# No_Opto_Flyback.net
KiCad netlist of a schematic drawn in Altium Designer
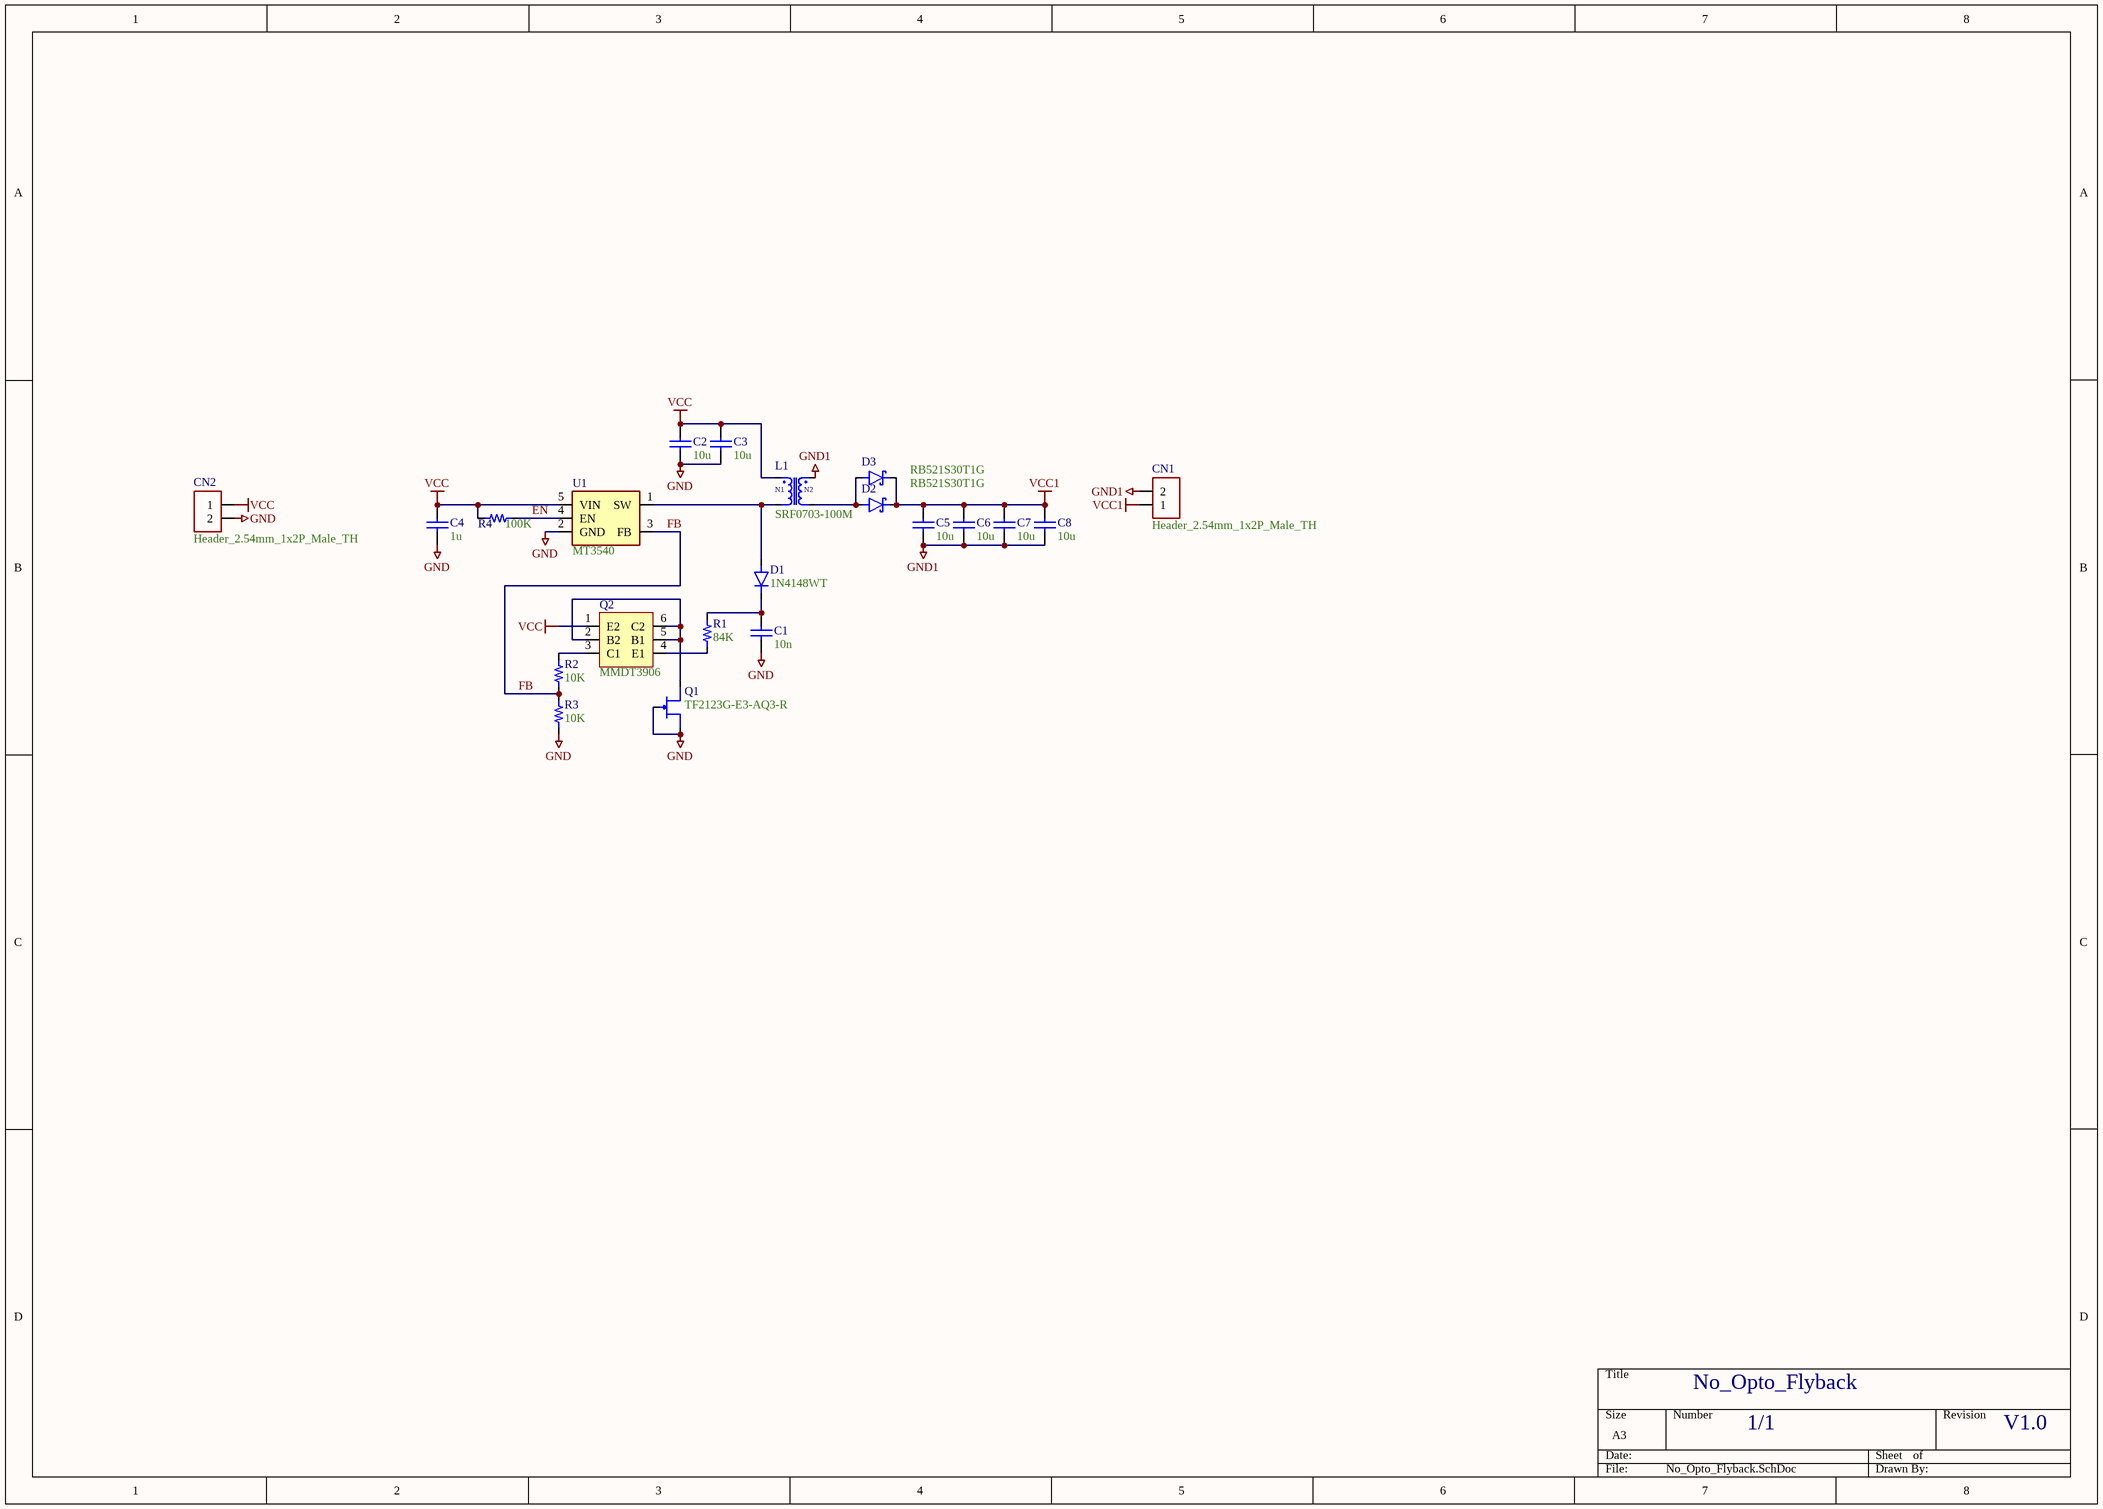
[diagram p0: No_Opto_Flyback.SchDoc]

(export (version "E")
  (design (tool "Eeschema 10.0.6"))
  (components
    (comp (ref "C1")
      (value "10n")
      (footprint "CAP_0402")
      (description "Capacitor")
      (fields (field (name "VOLTAGE") "V"))
      (libsource (lib "Passive") (part "Capacitor"))
    )
    (comp (ref "C2")
      (value "10u")
      (footprint "CAP_0603")
      (description "Capacitor")
      (fields (field (name "VOLTAGE") "V"))
      (libsource (lib "Passive") (part "Capacitor"))
    )
    (comp (ref "C3")
      (value "10u")
      (footprint "CAP_0603")
      (description "Capacitor")
      (fields (field (name "VOLTAGE") "V"))
      (libsource (lib "Passive") (part "Capacitor"))
    )
    (comp (ref "C4")
      (value "1u")
      (footprint "CAP_0402")
      (description "Capacitor")
      (fields (field (name "VOLTAGE") "V"))
      (libsource (lib "Passive") (part "Capacitor"))
    )
    (comp (ref "C5")
      (value "10u")
      (footprint "CAP_0603")
      (description "Capacitor")
      (fields (field (name "VOLTAGE") "V"))
      (libsource (lib "Passive") (part "Capacitor"))
    )
    (comp (ref "C6")
      (value "10u")
      (footprint "CAP_0603")
      (description "Capacitor")
      (fields (field (name "VOLTAGE") "V"))
      (libsource (lib "Passive") (part "Capacitor"))
    )
    (comp (ref "C7")
      (value "10u")
      (footprint "CAP_0603")
      (description "Capacitor")
      (fields (field (name "VOLTAGE") "V"))
      (libsource (lib "Passive") (part "Capacitor"))
    )
    (comp (ref "C8")
      (value "10u")
      (footprint "CAP_0603")
      (description "Capacitor")
      (fields (field (name "VOLTAGE") "V"))
      (libsource (lib "Passive") (part "Capacitor"))
    )
    (comp (ref "CN1")
      (value "Header_2.54mm_1x2P_Male_TH")
      (footprint "Header_2.54mm_1x2P_Male_TH")
      (description "Header_2.54mm_1x2P_Male\r\nThrough-hole")
      (libsource (lib "Connector") (part "Header_2.54mm_1x2P_Male_TH"))
    )
    (comp (ref "CN2")
      (value "Header_2.54mm_1x2P_Male_TH")
      (footprint "Header_2.54mm_1x2P_Male_TH")
      (description "Header_2.54mm_1x2P_Male\r\nThrough-hole")
      (libsource (lib "Connector") (part "Header_2.54mm_1x2P_Male_TH"))
    )
    (comp (ref "D1")
      (value "1N4148WT")
      (footprint "SOD-523-2")
      (description "Signal Diode")
      (libsource (lib "Diode") (part "1N4148WT"))
    )
    (comp (ref "D2")
      (value "RB521S30T1G")
      (footprint "SOD-523-2")
      (description "Schottky Diode")
      (libsource (lib "Diode") (part "RB521S30T1G"))
    )
    (comp (ref "D3")
      (value "RB521S30T1G")
      (footprint "SOD-523-2")
      (description "Schottky Diode")
      (libsource (lib "Diode") (part "RB521S30T1G"))
    )
    (comp (ref "L1")
      (value "SRF0703-100M")
      (footprint "SRF0703")
      (libsource (lib "Passive") (part "SRF0703-100M"))
    )
    (comp (ref "Q1")
      (value "TF2123G-E3-AQ3-R")
      (footprint "SOT-723-3_120X80X50_40P")
      (description "N-JFET")
      (libsource (lib "Transistor") (part "TF2123G-E3-AQ3-R"))
    )
    (comp (ref "Q2")
      (value "MMDT3906")
      (footprint "SOT-363-6_215X130X110_65P")
      (description "Double PNP")
      (libsource (lib "Transistor") (part "MMDT3906"))
    )
    (comp (ref "R1")
      (value "84K")
      (footprint "RES_0402")
      (description "Resistor")
      (fields (field (name "VOLTAGE") "V"))
      (libsource (lib "Passive") (part "Resistor"))
    )
    (comp (ref "R2")
      (value "10K")
      (footprint "RES_0402")
      (description "Resistor")
      (fields (field (name "VOLTAGE") "V"))
      (libsource (lib "Passive") (part "Resistor"))
    )
    (comp (ref "R3")
      (value "10K")
      (footprint "RES_0402")
      (description "Resistor")
      (fields (field (name "VOLTAGE") "V"))
      (libsource (lib "Passive") (part "Resistor"))
    )
    (comp (ref "R4")
      (value "100K")
      (footprint "RES_0402")
      (description "Resistor")
      (fields (field (name "VOLTAGE") "V"))
      (libsource (lib "Passive") (part "Resistor"))
    )
    (comp (ref "U1")
      (value "MT3540")
      (footprint "SOT-23-5_290X160X120_95P")
      (description "Asynchronous Boost Convertor\r\nVin:2.5~5.5V\r\nVout:Vin~28V")
      (libsource (lib "IC") (part "MT3540"))
    )
  )
  (nets
    (net (code "1") (name "/EN") (class "Default")
      (node (ref "R4") (pin "1") (pinfunction "1_1") (pintype "passive"))
      (node (ref "U1") (pin "4") (pinfunction "EN_4") (pintype "passive"))
    )
    (net (code "2") (name "/FB") (class "Default")
      (node (ref "R2") (pin "1") (pinfunction "1_1") (pintype "passive"))
      (node (ref "R3") (pin "2") (pinfunction "2_2") (pintype "passive"))
      (node (ref "U1") (pin "3") (pinfunction "FB_3") (pintype "passive"))
    )
    (net (code "3") (name "GND") (class "Default")
      (node (ref "C1") (pin "2") (pintype "passive"))
      (node (ref "C2") (pin "2") (pintype "passive"))
      (node (ref "C3") (pin "2") (pintype "passive"))
      (node (ref "C4") (pin "2") (pintype "passive"))
      (node (ref "CN2") (pin "2") (pinfunction "2_2") (pintype "passive"))
      (node (ref "Q1") (pin "2") (pinfunction "S_2") (pintype "passive"))
      (node (ref "Q1") (pin "3") (pinfunction "G_3") (pintype "passive"))
      (node (ref "R3") (pin "1") (pinfunction "1_1") (pintype "passive"))
      (node (ref "U1") (pin "2") (pinfunction "GND_2") (pintype "passive"))
    )
    (net (code "4") (name "GND1") (class "Default")
      (node (ref "C5") (pin "2") (pintype "passive"))
      (node (ref "C6") (pin "2") (pintype "passive"))
      (node (ref "C7") (pin "2") (pintype "passive"))
      (node (ref "C8") (pin "2") (pintype "passive"))
      (node (ref "CN1") (pin "2") (pinfunction "2_2") (pintype "passive"))
      (node (ref "L1") (pin "2") (pinfunction "2_2") (pintype "passive"))
    )
    (net (code "5") (name "Net-(D1-A)") (class "Default")
      (node (ref "D1") (pin "2") (pinfunction "A_2") (pintype "passive"))
      (node (ref "L1") (pin "3") (pinfunction "3_3") (pintype "passive"))
      (node (ref "U1") (pin "1") (pinfunction "SW_1") (pintype "passive"))
    )
    (net (code "6") (name "Net-(D1-K)") (class "Default")
      (node (ref "C1") (pin "1") (pintype "passive"))
      (node (ref "D1") (pin "1") (pinfunction "K_1") (pintype "passive"))
      (node (ref "R1") (pin "2") (pinfunction "2_2") (pintype "passive"))
    )
    (net (code "7") (name "Net-(D2-A)") (class "Default")
      (node (ref "D2") (pin "2") (pinfunction "A_2") (pintype "passive"))
      (node (ref "D3") (pin "2") (pinfunction "A_2") (pintype "passive"))
      (node (ref "L1") (pin "4") (pinfunction "4_4") (pintype "passive"))
    )
    (net (code "8") (name "Net-(Q1-D)") (class "Default")
      (node (ref "Q1") (pin "1") (pinfunction "D_1") (pintype "passive"))
      (node (ref "Q2") (pin "2") (pinfunction "B2_2") (pintype "passive"))
      (node (ref "Q2") (pin "5") (pinfunction "B1_5") (pintype "passive"))
      (node (ref "Q2") (pin "6") (pinfunction "C2_6") (pintype "passive"))
    )
    (net (code "9") (name "Net-(Q2-C1)") (class "Default")
      (node (ref "Q2") (pin "3") (pinfunction "C1_3") (pintype "passive"))
      (node (ref "R2") (pin "2") (pinfunction "2_2") (pintype "passive"))
    )
    (net (code "10") (name "Net-(Q2-E1)") (class "Default")
      (node (ref "Q2") (pin "4") (pinfunction "E1_4") (pintype "passive"))
      (node (ref "R1") (pin "1") (pinfunction "1_1") (pintype "passive"))
    )
    (net (code "11") (name "VCC") (class "Default")
      (node (ref "C2") (pin "1") (pintype "passive"))
      (node (ref "C3") (pin "1") (pintype "passive"))
      (node (ref "C4") (pin "1") (pintype "passive"))
      (node (ref "CN2") (pin "1") (pinfunction "1_1") (pintype "passive"))
      (node (ref "L1") (pin "1") (pinfunction "1_1") (pintype "passive"))
      (node (ref "Q2") (pin "1") (pinfunction "E2_1") (pintype "passive"))
      (node (ref "R4") (pin "2") (pinfunction "2_2") (pintype "passive"))
      (node (ref "U1") (pin "5") (pinfunction "VIN_5") (pintype "passive"))
    )
    (net (code "12") (name "VCC1") (class "Default")
      (node (ref "C5") (pin "1") (pintype "passive"))
      (node (ref "C6") (pin "1") (pintype "passive"))
      (node (ref "C7") (pin "1") (pintype "passive"))
      (node (ref "C8") (pin "1") (pintype "passive"))
      (node (ref "CN1") (pin "1") (pinfunction "1_1") (pintype "passive"))
      (node (ref "D2") (pin "1") (pinfunction "K_1") (pintype "passive"))
      (node (ref "D3") (pin "1") (pinfunction "K_1") (pintype "passive"))
    )
  )
)
